# 5_RK3399_EDP_CSI_HDMI.net
KiCad netlist of a schematic drawn in Altium Designer
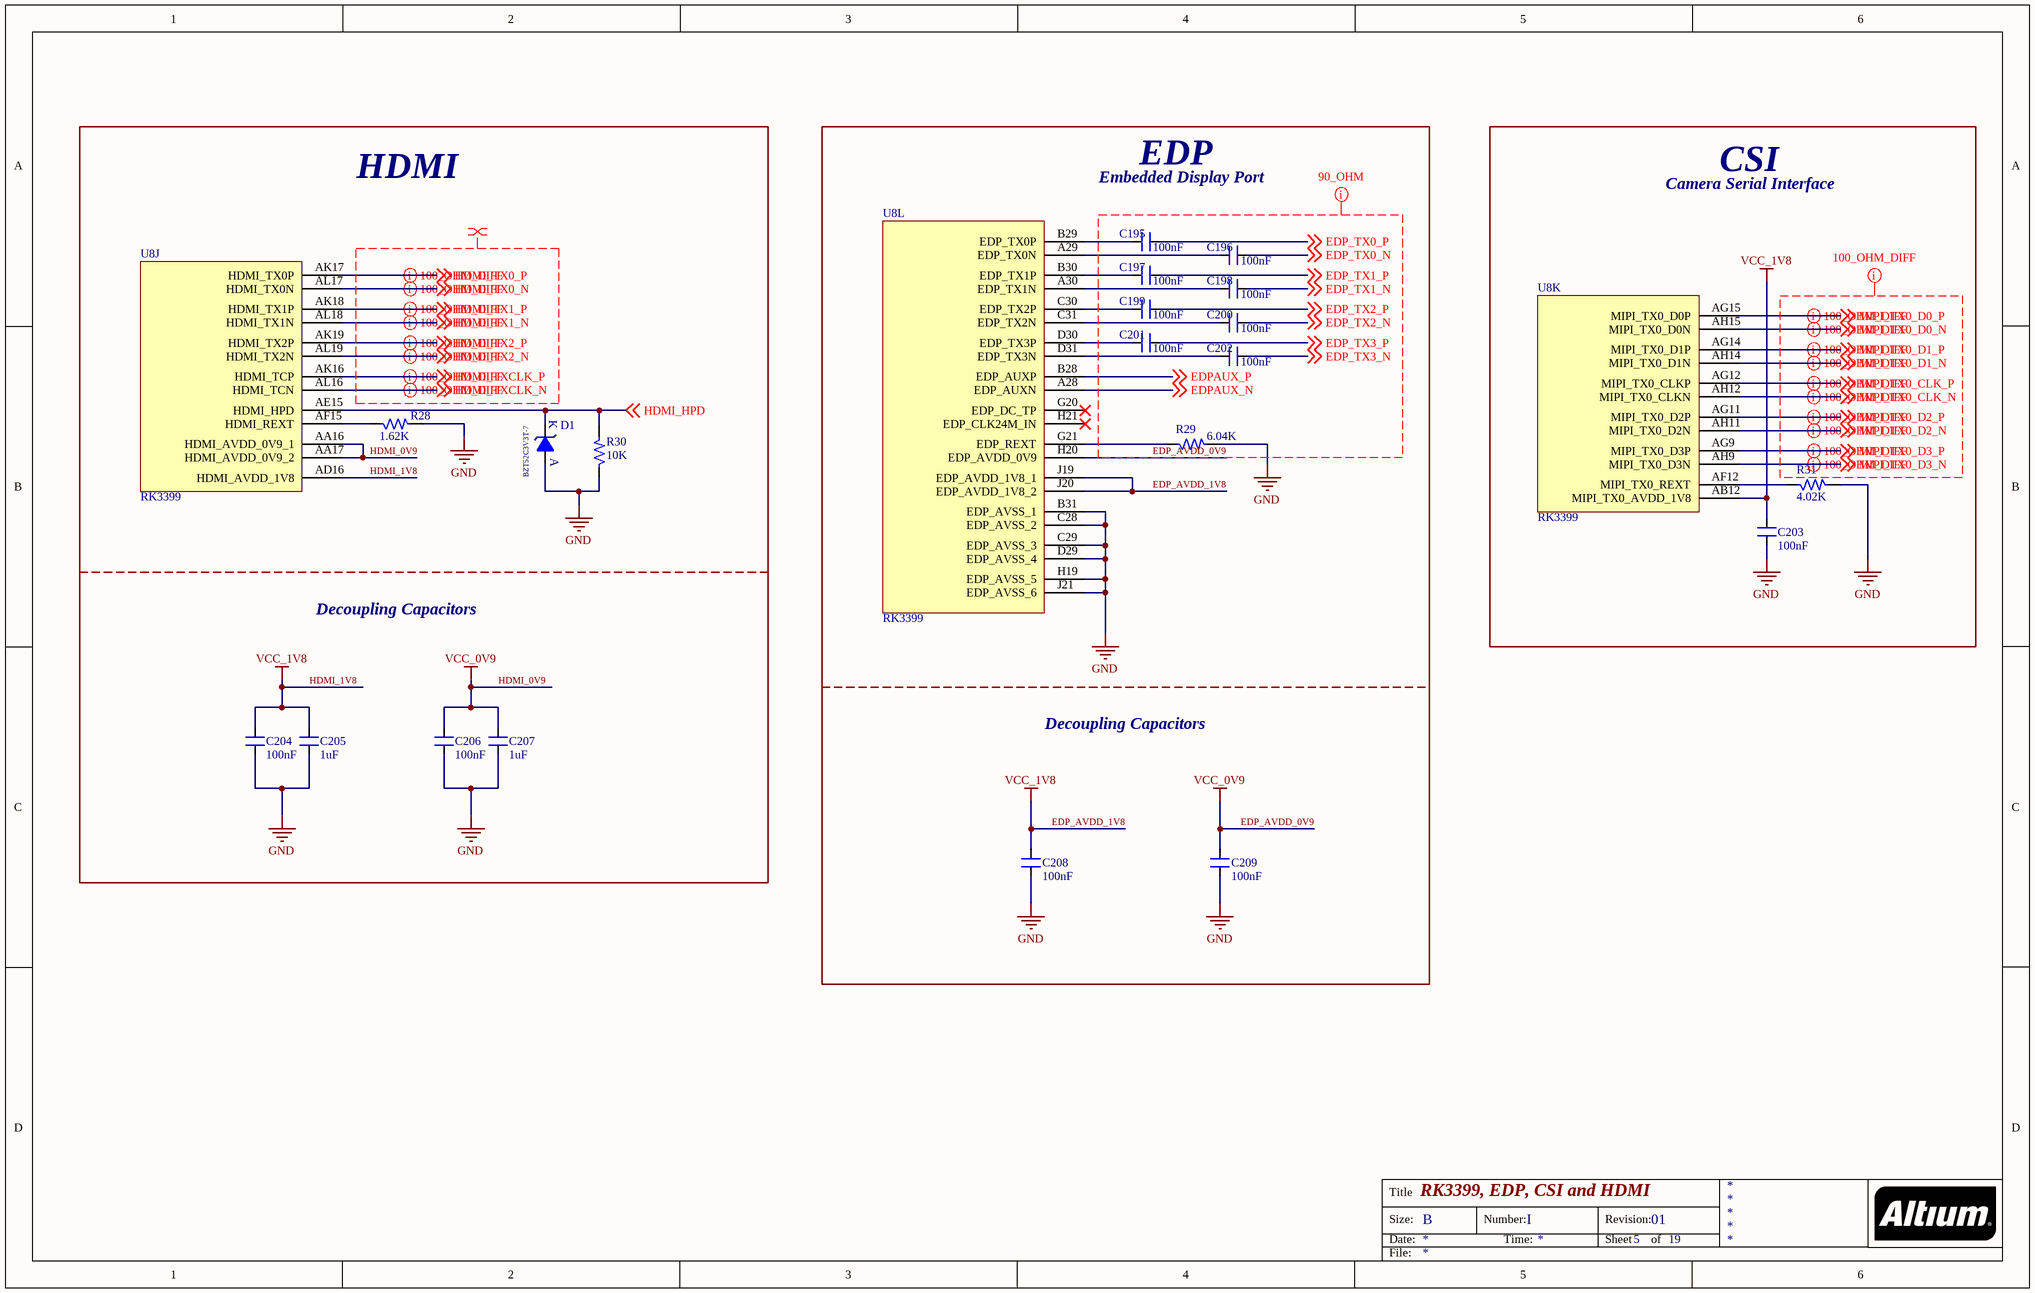
[diagram p0: [5] RK3399_EDP_CSI_HDMI.SchDoc]

(export (version "E")
  (design (tool "Eeschema 10.0.6"))
  (components
    (comp (ref "C195")
      (value "100nF")
      (footprint "CAP_0201")
      (description "0.1µF ±10% 25V Ceramic Capacitor X5R 0201 (0603 Metric)")
      (fields
        (field (name "MANUFACTURER") "TDK Corporation")
        (field (name "MANUFACTURER PART NUMBER") "C0603X5R1E104K030BB")
      )
      (libsource (lib "EsteemPCB_SOM_Course_intlib") (part "CAP_100nF-25V-10%-0201"))
    )
    (comp (ref "C196")
      (value "100nF")
      (footprint "CAP_0201")
      (description "0.1µF ±10% 25V Ceramic Capacitor X5R 0201 (0603 Metric)")
      (fields
        (field (name "MANUFACTURER") "TDK Corporation")
        (field (name "MANUFACTURER PART NUMBER") "C0603X5R1E104K030BB")
      )
      (libsource (lib "EsteemPCB_SOM_Course_intlib") (part "CAP_100nF-25V-10%-0201"))
    )
    (comp (ref "C197")
      (value "100nF")
      (footprint "CAP_0201")
      (description "0.1µF ±10% 25V Ceramic Capacitor X5R 0201 (0603 Metric)")
      (fields
        (field (name "MANUFACTURER") "TDK Corporation")
        (field (name "MANUFACTURER PART NUMBER") "C0603X5R1E104K030BB")
      )
      (libsource (lib "EsteemPCB_SOM_Course_intlib") (part "CAP_100nF-25V-10%-0201"))
    )
    (comp (ref "C198")
      (value "100nF")
      (footprint "CAP_0201")
      (description "0.1µF ±10% 25V Ceramic Capacitor X5R 0201 (0603 Metric)")
      (fields
        (field (name "MANUFACTURER") "TDK Corporation")
        (field (name "MANUFACTURER PART NUMBER") "C0603X5R1E104K030BB")
      )
      (libsource (lib "EsteemPCB_SOM_Course_intlib") (part "CAP_100nF-25V-10%-0201"))
    )
    (comp (ref "C199")
      (value "100nF")
      (footprint "CAP_0201")
      (description "0.1µF ±10% 25V Ceramic Capacitor X5R 0201 (0603 Metric)")
      (fields
        (field (name "MANUFACTURER") "TDK Corporation")
        (field (name "MANUFACTURER PART NUMBER") "C0603X5R1E104K030BB")
      )
      (libsource (lib "EsteemPCB_SOM_Course_intlib") (part "CAP_100nF-25V-10%-0201"))
    )
    (comp (ref "C200")
      (value "100nF")
      (footprint "CAP_0201")
      (description "0.1µF ±10% 25V Ceramic Capacitor X5R 0201 (0603 Metric)")
      (fields
        (field (name "MANUFACTURER") "TDK Corporation")
        (field (name "MANUFACTURER PART NUMBER") "C0603X5R1E104K030BB")
      )
      (libsource (lib "EsteemPCB_SOM_Course_intlib") (part "CAP_100nF-25V-10%-0201"))
    )
    (comp (ref "C201")
      (value "100nF")
      (footprint "CAP_0201")
      (description "0.1µF ±10% 25V Ceramic Capacitor X5R 0201 (0603 Metric)")
      (fields
        (field (name "MANUFACTURER") "TDK Corporation")
        (field (name "MANUFACTURER PART NUMBER") "C0603X5R1E104K030BB")
      )
      (libsource (lib "EsteemPCB_SOM_Course_intlib") (part "CAP_100nF-25V-10%-0201"))
    )
    (comp (ref "C202")
      (value "100nF")
      (footprint "CAP_0201")
      (description "0.1µF ±10% 25V Ceramic Capacitor X5R 0201 (0603 Metric)")
      (fields
        (field (name "MANUFACTURER") "TDK Corporation")
        (field (name "MANUFACTURER PART NUMBER") "C0603X5R1E104K030BB")
      )
      (libsource (lib "EsteemPCB_SOM_Course_intlib") (part "CAP_100nF-25V-10%-0201"))
    )
    (comp (ref "C203")
      (value "100nF")
      (footprint "CAP_0201")
      (description "0.1µF ±10% 25V Ceramic Capacitor X5R 0201 (0603 Metric)")
      (fields
        (field (name "MANUFACTURER") "TDK Corporation")
        (field (name "MANUFACTURER PART NUMBER") "C0603X5R1E104K030BB")
      )
      (libsource (lib "EsteemPCB_SOM_Course_intlib") (part "CAP_100nF-25V-10%-0201"))
    )
    (comp (ref "C204")
      (value "100nF")
      (footprint "CAP_0201")
      (description "0.1µF ±10% 25V Ceramic Capacitor X5R 0201 (0603 Metric)")
      (fields
        (field (name "MANUFACTURER") "TDK Corporation")
        (field (name "MANUFACTURER PART NUMBER") "C0603X5R1E104K030BB")
      )
      (libsource (lib "EsteemPCB_SOM_Course_intlib") (part "CAP_100nF-25V-10%-0201"))
    )
    (comp (ref "C205")
      (value "1uF")
      (footprint "CAP_0201")
      (description "1µF ±20% 16V Ceramic Capacitor X5R 0201 (0603 Metric)")
      (fields
        (field (name "MANUFACTURER") "Samsung Electro-Mechanics")
        (field (name "MANUFACTURER PART NUMBER") "CL03A105MO3NRNH")
      )
      (libsource (lib "EsteemPCB_SOM_Course_intlib") (part "CAP_1uF-16V-10%-0201"))
    )
    (comp (ref "C206")
      (value "100nF")
      (footprint "CAP_0201")
      (description "0.1µF ±10% 25V Ceramic Capacitor X5R 0201 (0603 Metric)")
      (fields
        (field (name "MANUFACTURER") "TDK Corporation")
        (field (name "MANUFACTURER PART NUMBER") "C0603X5R1E104K030BB")
      )
      (libsource (lib "EsteemPCB_SOM_Course_intlib") (part "CAP_100nF-25V-10%-0201"))
    )
    (comp (ref "C207")
      (value "1uF")
      (footprint "CAP_0201")
      (description "1µF ±20% 16V Ceramic Capacitor X5R 0201 (0603 Metric)")
      (fields
        (field (name "MANUFACTURER") "Samsung Electro-Mechanics")
        (field (name "MANUFACTURER PART NUMBER") "CL03A105MO3NRNH")
      )
      (libsource (lib "EsteemPCB_SOM_Course_intlib") (part "CAP_1uF-16V-10%-0201"))
    )
    (comp (ref "C208")
      (value "100nF")
      (footprint "CAP_0201")
      (description "0.1µF ±10% 25V Ceramic Capacitor X5R 0201 (0603 Metric)")
      (fields
        (field (name "MANUFACTURER") "TDK Corporation")
        (field (name "MANUFACTURER PART NUMBER") "C0603X5R1E104K030BB")
      )
      (libsource (lib "EsteemPCB_SOM_Course_intlib") (part "CAP_100nF-25V-10%-0201"))
    )
    (comp (ref "C209")
      (value "100nF")
      (footprint "CAP_0201")
      (description "0.1µF ±10% 25V Ceramic Capacitor X5R 0201 (0603 Metric)")
      (fields
        (field (name "MANUFACTURER") "TDK Corporation")
        (field (name "MANUFACTURER PART NUMBER") "C0603X5R1E104K030BB")
      )
      (libsource (lib "EsteemPCB_SOM_Course_intlib") (part "CAP_100nF-25V-10%-0201"))
    )
    (comp (ref "D1")
      (value "BZT52C3V3T-7")
      (footprint "DIO_SOD523")
      (description "Zener Diode 3.3V 300mW ±6% Surface Mount SOD-523")
      (fields (field (name "MANUFACTURER") "Diodes Incorporated"))
      (libsource (lib "EsteemPCB_SOM_Course_intlib") (part "DIO-Z_3.3V-300mW-SOD-523"))
    )
    (comp (ref "R28")
      (value "1.62K")
      (footprint "RES_0201")
      (description "1.62 kOhms ±1% 0.05W, 1/20W Chip Resistor 0201 (0603 Metric) Automotive AEC-Q200 Thick Film")
      (fields
        (field (name "MANUFACTURER") "Panasonic Electronic Components")
        (field (name "MANUFACTURER PART NUMBER") "ERJ-1GNF1621C")
      )
      (libsource (lib "EsteemPCB_SOM_Course_intlib") (part "RES_1.62K-0.05W-1%-0201"))
    )
    (comp (ref "R29")
      (value "6.04K")
      (footprint "RES_0201")
      (description "6.04 kOhms ±1% 0.05W, 1/20W Chip Resistor 0201 (0603 Metric) Thick Film")
      (fields
        (field (name "MANUFACTURER") "Panasonic Electronic Components")
        (field (name "MANUFACTURER PART NUMBER") "ERJ-1GEF6041C")
      )
      (libsource (lib "EsteemPCB_SOM_Course_intlib") (part "RES_6.04K-0.05W-1%-0201"))
    )
    (comp (ref "R30")
      (value "10K")
      (footprint "RES_0201")
      (description "10 kOhms ±1% 0.05W, 1/20W Chip Resistor 0201 (0603 Metric) Thick Film")
      (fields
        (field (name "MANUFACTURER") "Stackpole Electronics Inc")
        (field (name "MANUFACTURER PART NUMBER") "RMCF0201FT10K0")
      )
      (libsource (lib "EsteemPCB_SOM_Course_intlib") (part "RES_10K-0.05W-1%-0201"))
    )
    (comp (ref "R31")
      (value "4.02K")
      (footprint "RES_0201")
      (description "4.02 kOhms ±1% 0.05W, 1/20W Chip Resistor 0201 (0603 Metric) Thick Film")
      (fields
        (field (name "MANUFACTURER") "Yageo")
        (field (name "MANUFACTURER PART NUMBER") "RC0201FR-074K02L")
      )
      (libsource (lib "EsteemPCB_SOM_Course_intlib") (part "RES_4.02K-0.05W-1%-0201"))
    )
    (comp (ref "U8")
      (value "RK3399")
      (footprint "FBGA828_23_826X826")
      (description "RK3399 is a low power, high performance processor for computing, personal mobile.")
      (fields (field (name "MANUFACTURER") "Rockchip"))
      (libsource (lib "EsteemPCB_SOM_Course_intlib") (part "IC_RK3399-FCBGA828"))
    )
  )
  (nets
    (net (code "1") (name "EDPAUX_N") (class "Default")
      (node (ref "U8") (pin "A28") (pinfunction "EDP_AUXN_A28") (pintype "passive"))
    )
    (net (code "2") (name "EDPAUX_P") (class "Default")
      (node (ref "U8") (pin "B28") (pinfunction "EDP_AUXP_B28") (pintype "passive"))
    )
    (net (code "3") (name "EDP_TX0_N") (class "Default")
      (node (ref "C196") (pin "2") (pinfunction "2_2") (pintype "passive"))
    )
    (net (code "4") (name "EDP_TX0_P") (class "Default")
      (node (ref "C195") (pin "2") (pinfunction "2_2") (pintype "passive"))
    )
    (net (code "5") (name "EDP_TX1_N") (class "Default")
      (node (ref "C198") (pin "2") (pinfunction "2_2") (pintype "passive"))
    )
    (net (code "6") (name "EDP_TX1_P") (class "Default")
      (node (ref "C197") (pin "2") (pinfunction "2_2") (pintype "passive"))
    )
    (net (code "7") (name "EDP_TX2_N") (class "Default")
      (node (ref "C200") (pin "2") (pinfunction "2_2") (pintype "passive"))
    )
    (net (code "8") (name "EDP_TX2_P") (class "Default")
      (node (ref "C199") (pin "2") (pinfunction "2_2") (pintype "passive"))
    )
    (net (code "9") (name "EDP_TX3_N") (class "Default")
      (node (ref "C202") (pin "2") (pinfunction "2_2") (pintype "passive"))
    )
    (net (code "10") (name "EDP_TX3_P") (class "Default")
      (node (ref "C201") (pin "2") (pinfunction "2_2") (pintype "passive"))
    )
    (net (code "11") (name "GND") (class "Default")
      (node (ref "C203") (pin "1") (pinfunction "1_1") (pintype "passive"))
      (node (ref "C204") (pin "1") (pinfunction "1_1") (pintype "passive"))
      (node (ref "C205") (pin "1") (pinfunction "1_1") (pintype "passive"))
      (node (ref "C206") (pin "1") (pinfunction "1_1") (pintype "passive"))
      (node (ref "C207") (pin "1") (pinfunction "1_1") (pintype "passive"))
      (node (ref "C208") (pin "1") (pinfunction "1_1") (pintype "passive"))
      (node (ref "C209") (pin "1") (pinfunction "1_1") (pintype "passive"))
      (node (ref "D1") (pin "A") (pinfunction "A_A") (pintype "passive"))
      (node (ref "R28") (pin "2") (pinfunction "2_2") (pintype "passive"))
      (node (ref "R29") (pin "2") (pinfunction "2_2") (pintype "passive"))
      (node (ref "R30") (pin "1") (pinfunction "1_1") (pintype "passive"))
      (node (ref "R31") (pin "2") (pinfunction "2_2") (pintype "passive"))
      (node (ref "U8") (pin "B31") (pinfunction "EDP_AVSS_1_B31") (pintype "passive"))
      (node (ref "U8") (pin "C28") (pinfunction "EDP_AVSS_2_C28") (pintype "passive"))
      (node (ref "U8") (pin "C29") (pinfunction "EDP_AVSS_3_C29") (pintype "passive"))
      (node (ref "U8") (pin "D29") (pinfunction "EDP_AVSS_4_D29") (pintype "passive"))
      (node (ref "U8") (pin "H19") (pinfunction "EDP_AVSS_5_H19") (pintype "passive"))
      (node (ref "U8") (pin "J21") (pinfunction "EDP_AVSS_6_J21") (pintype "passive"))
    )
    (net (code "12") (name "HDMI_HPD") (class "Default")
      (node (ref "D1") (pin "K") (pinfunction "K_K") (pintype "passive"))
      (node (ref "R30") (pin "2") (pinfunction "2_2") (pintype "passive"))
      (node (ref "U8") (pin "AE15") (pinfunction "HDMI_HPD_AE15") (pintype "passive"))
    )
    (net (code "13") (name "HDMI_TX0_N") (class "Default")
      (node (ref "U8") (pin "AL17") (pinfunction "HDMI_TX0N_AL17") (pintype "passive"))
    )
    (net (code "14") (name "HDMI_TX0_P") (class "Default")
      (node (ref "U8") (pin "AK17") (pinfunction "HDMI_TX0P_AK17") (pintype "passive"))
    )
    (net (code "15") (name "HDMI_TX1_N") (class "Default")
      (node (ref "U8") (pin "AL18") (pinfunction "HDMI_TX1N_AL18") (pintype "passive"))
    )
    (net (code "16") (name "HDMI_TX1_P") (class "Default")
      (node (ref "U8") (pin "AK18") (pinfunction "HDMI_TX1P_AK18") (pintype "passive"))
    )
    (net (code "17") (name "HDMI_TX2_N") (class "Default")
      (node (ref "U8") (pin "AL19") (pinfunction "HDMI_TX2N_AL19") (pintype "passive"))
    )
    (net (code "18") (name "HDMI_TX2_P") (class "Default")
      (node (ref "U8") (pin "AK19") (pinfunction "HDMI_TX2P_AK19") (pintype "passive"))
    )
    (net (code "19") (name "HDMI_TXCLK_N") (class "Default")
      (node (ref "U8") (pin "AL16") (pinfunction "HDMI_TCN_AL16") (pintype "passive"))
    )
    (net (code "20") (name "HDMI_TXCLK_P") (class "Default")
      (node (ref "U8") (pin "AK16") (pinfunction "HDMI_TCP_AK16") (pintype "passive"))
    )
    (net (code "21") (name "MIPI_TX0_CLK_N") (class "Default")
      (node (ref "U8") (pin "AH12") (pinfunction "MIPI_TX0_CLKN_AH12") (pintype "passive"))
    )
    (net (code "22") (name "MIPI_TX0_CLK_P") (class "Default")
      (node (ref "U8") (pin "AG12") (pinfunction "MIPI_TX0_CLKP_AG12") (pintype "passive"))
    )
    (net (code "23") (name "MIPI_TX0_D0_N") (class "Default")
      (node (ref "U8") (pin "AH15") (pinfunction "MIPI_TX0_D0N_AH15") (pintype "passive"))
    )
    (net (code "24") (name "MIPI_TX0_D0_P") (class "Default")
      (node (ref "U8") (pin "AG15") (pinfunction "MIPI_TX0_D0P_AG15") (pintype "passive"))
    )
    (net (code "25") (name "MIPI_TX0_D1_N") (class "Default")
      (node (ref "U8") (pin "AH14") (pinfunction "MIPI_TX0_D1N_AH14") (pintype "passive"))
    )
    (net (code "26") (name "MIPI_TX0_D1_P") (class "Default")
      (node (ref "U8") (pin "AG14") (pinfunction "MIPI_TX0_D1P_AG14") (pintype "passive"))
    )
    (net (code "27") (name "MIPI_TX0_D2_N") (class "Default")
      (node (ref "U8") (pin "AH11") (pinfunction "MIPI_TX0_D2N_AH11") (pintype "passive"))
    )
    (net (code "28") (name "MIPI_TX0_D2_P") (class "Default")
      (node (ref "U8") (pin "AG11") (pinfunction "MIPI_TX0_D2P_AG11") (pintype "passive"))
    )
    (net (code "29") (name "MIPI_TX0_D3_N") (class "Default")
      (node (ref "U8") (pin "AH9") (pinfunction "MIPI_TX0_D3N_AH9") (pintype "passive"))
    )
    (net (code "30") (name "MIPI_TX0_D3_P") (class "Default")
      (node (ref "U8") (pin "AG9") (pinfunction "MIPI_TX0_D3P_AG9") (pintype "passive"))
    )
    (net (code "31") (name "Net-(U8J-HDMI_REXT)") (class "Default")
      (node (ref "R28") (pin "1") (pinfunction "1_1") (pintype "passive"))
      (node (ref "U8") (pin "AF15") (pinfunction "HDMI_REXT_AF15") (pintype "passive"))
    )
    (net (code "32") (name "Net-(U8K-MIPI_TX0_REXT)") (class "Default")
      (node (ref "R31") (pin "1") (pinfunction "1_1") (pintype "passive"))
      (node (ref "U8") (pin "AF12") (pinfunction "MIPI_TX0_REXT_AF12") (pintype "passive"))
    )
    (net (code "33") (name "Net-(U8L-EDP_REXT)") (class "Default")
      (node (ref "R29") (pin "1") (pinfunction "1_1") (pintype "passive"))
      (node (ref "U8") (pin "G21") (pinfunction "EDP_REXT_G21") (pintype "passive"))
    )
    (net (code "34") (name "Net-(U8L-EDP_TX0N)") (class "Default")
      (node (ref "C196") (pin "1") (pinfunction "1_1") (pintype "passive"))
      (node (ref "U8") (pin "A29") (pinfunction "EDP_TX0N_A29") (pintype "passive"))
    )
    (net (code "35") (name "Net-(U8L-EDP_TX0P)") (class "Default")
      (node (ref "C195") (pin "1") (pinfunction "1_1") (pintype "passive"))
      (node (ref "U8") (pin "B29") (pinfunction "EDP_TX0P_B29") (pintype "passive"))
    )
    (net (code "36") (name "Net-(U8L-EDP_TX1N)") (class "Default")
      (node (ref "C198") (pin "1") (pinfunction "1_1") (pintype "passive"))
      (node (ref "U8") (pin "A30") (pinfunction "EDP_TX1N_A30") (pintype "passive"))
    )
    (net (code "37") (name "Net-(U8L-EDP_TX1P)") (class "Default")
      (node (ref "C197") (pin "1") (pinfunction "1_1") (pintype "passive"))
      (node (ref "U8") (pin "B30") (pinfunction "EDP_TX1P_B30") (pintype "passive"))
    )
    (net (code "38") (name "Net-(U8L-EDP_TX2N)") (class "Default")
      (node (ref "C200") (pin "1") (pinfunction "1_1") (pintype "passive"))
      (node (ref "U8") (pin "C31") (pinfunction "EDP_TX2N_C31") (pintype "passive"))
    )
    (net (code "39") (name "Net-(U8L-EDP_TX2P)") (class "Default")
      (node (ref "C199") (pin "1") (pinfunction "1_1") (pintype "passive"))
      (node (ref "U8") (pin "C30") (pinfunction "EDP_TX2P_C30") (pintype "passive"))
    )
    (net (code "40") (name "Net-(U8L-EDP_TX3N)") (class "Default")
      (node (ref "C202") (pin "1") (pinfunction "1_1") (pintype "passive"))
      (node (ref "U8") (pin "D31") (pinfunction "EDP_TX3N_D31") (pintype "passive"))
    )
    (net (code "41") (name "Net-(U8L-EDP_TX3P)") (class "Default")
      (node (ref "C201") (pin "1") (pinfunction "1_1") (pintype "passive"))
      (node (ref "U8") (pin "D30") (pinfunction "EDP_TX3P_D30") (pintype "passive"))
    )
    (net (code "42") (name "VCC_0V9") (class "Default")
      (node (ref "C206") (pin "2") (pinfunction "2_2") (pintype "passive"))
      (node (ref "C207") (pin "2") (pinfunction "2_2") (pintype "passive"))
      (node (ref "C209") (pin "2") (pinfunction "2_2") (pintype "passive"))
      (node (ref "U8") (pin "AA16") (pinfunction "HDMI_AVDD_0V9_1_AA16") (pintype "passive"))
      (node (ref "U8") (pin "AA17") (pinfunction "HDMI_AVDD_0V9_2_AA17") (pintype "passive"))
      (node (ref "U8") (pin "H20") (pinfunction "EDP_AVDD_0V9_H20") (pintype "passive"))
    )
    (net (code "43") (name "VCC_1V8") (class "Default")
      (node (ref "C203") (pin "2") (pinfunction "2_2") (pintype "passive"))
      (node (ref "C204") (pin "2") (pinfunction "2_2") (pintype "passive"))
      (node (ref "C205") (pin "2") (pinfunction "2_2") (pintype "passive"))
      (node (ref "C208") (pin "2") (pinfunction "2_2") (pintype "passive"))
      (node (ref "U8") (pin "AB12") (pinfunction "MIPI_TX0_AVDD_1V8_AB12") (pintype "passive"))
      (node (ref "U8") (pin "AD16") (pinfunction "HDMI_AVDD_1V8_AD16") (pintype "passive"))
      (node (ref "U8") (pin "J19") (pinfunction "EDP_AVDD_1V8_1_J19") (pintype "passive"))
      (node (ref "U8") (pin "J20") (pinfunction "EDP_AVDD_1V8_2_J20") (pintype "passive"))
    )
    (net (code "44") (name "unconnected-(U8L-EDP_CLK24M_IN-PadH21)") (class "Default")
      (node (ref "U8") (pin "H21") (pinfunction "EDP_CLK24M_IN_H21") (pintype "passive+no_connect"))
    )
    (net (code "45") (name "unconnected-(U8L-EDP_DC_TP-PadG20)") (class "Default")
      (node (ref "U8") (pin "G20") (pinfunction "EDP_DC_TP_G20") (pintype "passive+no_connect"))
    )
  )
)
